# humidor_controller_v32.net
KiCad netlist of a schematic drawn in EAGLE
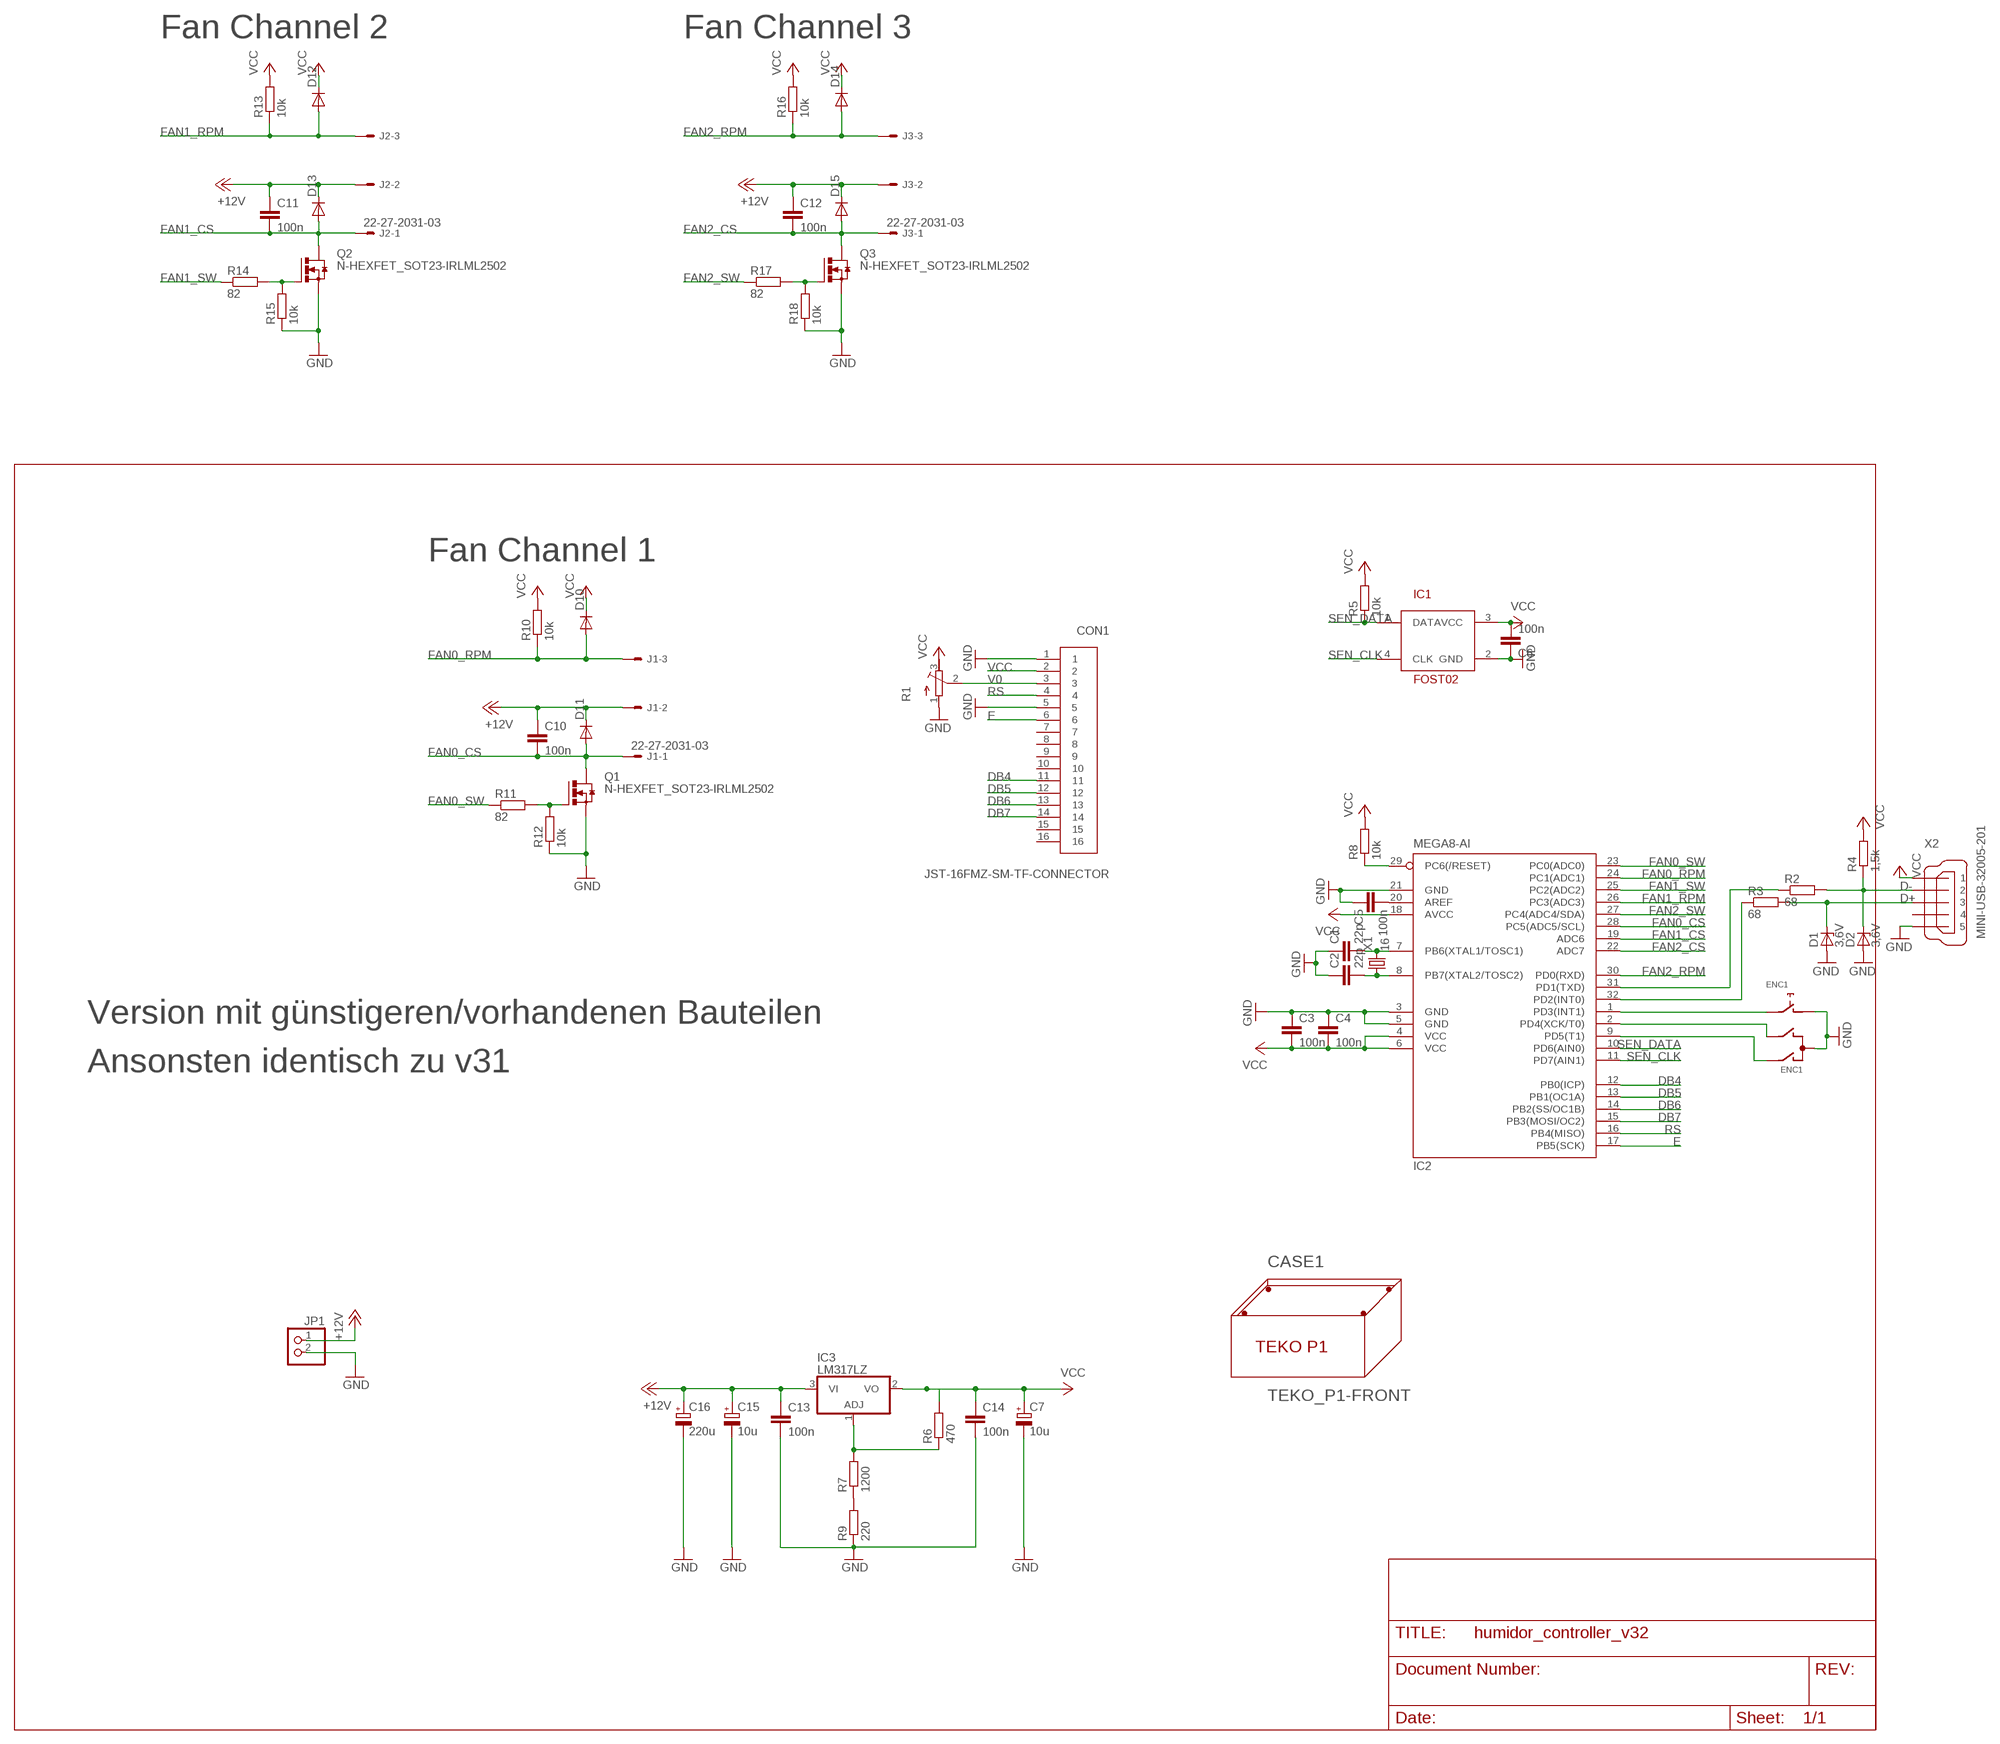
[diagram p0: schematic, sheet 1]

(export (version "E")
  (design (tool "Eeschema 10.0.6"))
  (components
    (comp (ref "C1")
      (value "22p")
      (footprint "eagle-import:C0805")
      (libsource (lib "eagle-import") (part "C-EUC0805"))
    )
    (comp (ref "C2")
      (value "22p")
      (footprint "eagle-import:C0805")
      (libsource (lib "eagle-import") (part "C-EUC0805"))
    )
    (comp (ref "C3")
      (value "100n")
      (footprint "eagle-import:C0805")
      (libsource (lib "eagle-import") (part "resistor_C-EUC0805"))
    )
    (comp (ref "C4")
      (value "100n")
      (footprint "eagle-import:C0805")
      (libsource (lib "eagle-import") (part "resistor_C-EUC0805"))
    )
    (comp (ref "C5")
      (value "100n")
      (footprint "eagle-import:C0805")
      (libsource (lib "eagle-import") (part "resistor_C-EUC0805"))
    )
    (comp (ref "C6")
      (value "100n")
      (footprint "eagle-import:C0805")
      (libsource (lib "eagle-import") (part "resistor_C-EUC0805"))
    )
    (comp (ref "C7")
      (value "10u")
      (footprint "eagle-import:PANASONIC_D")
      (libsource (lib "eagle-import") (part "CPOL-EUD"))
    )
    (comp (ref "C10")
      (value "100n")
      (footprint "eagle-import:C0805")
      (libsource (lib "eagle-import") (part "resistor_C-EUC0805"))
    )
    (comp (ref "C11")
      (value "100n")
      (footprint "eagle-import:C0805")
      (libsource (lib "eagle-import") (part "resistor_C-EUC0805"))
    )
    (comp (ref "C12")
      (value "100n")
      (footprint "eagle-import:C0805")
      (libsource (lib "eagle-import") (part "resistor_C-EUC0805"))
    )
    (comp (ref "C13")
      (value "100n")
      (footprint "eagle-import:C0805")
      (libsource (lib "eagle-import") (part "C-EUC0805"))
    )
    (comp (ref "C14")
      (value "100n")
      (footprint "eagle-import:C0805")
      (libsource (lib "eagle-import") (part "C-EUC0805"))
    )
    (comp (ref "C15")
      (value "10u")
      (footprint "eagle-import:PANASONIC_D")
      (libsource (lib "eagle-import") (part "CPOL-EUD"))
    )
    (comp (ref "C16")
      (value "220u")
      (footprint "eagle-import:PANASONIC_G")
      (libsource (lib "eagle-import") (part "CPOL-EUG"))
    )
    (comp (ref "CASE1")
      (value "TEKO_P1-FRONT")
      (footprint "eagle-import:TEKO_P1_FRONT")
      (libsource (lib "eagle-import") (part "TEKO_P1-FRONT"))
    )
    (comp (ref "CON1")
      (value "JST-16FMZ-SM-TF-CONNECTOR")
      (footprint "eagle-import:FFC-16POS-SMT-1MM-HORIZ")
      (libsource (lib "eagle-import") (part "JST-16FMZ-SM-TF-CONNECTOR"))
    )
    (comp (ref "D1")
      (value "3,6V")
      (footprint "eagle-import:DO34Z7")
      (libsource (lib "eagle-import") (part "ZENER-DIODEDO34-7"))
    )
    (comp (ref "D2")
      (value "3,6V")
      (footprint "eagle-import:DO34Z7")
      (libsource (lib "eagle-import") (part "ZENER-DIODEDO34-7"))
    )
    (comp (ref "D10")
      (value "DIODE-SOD323-R")
      (footprint "eagle-import:SOD323-R")
      (libsource (lib "eagle-import") (part "DIODE-SOD323-R"))
    )
    (comp (ref "D11")
      (value "DIODE-SOD323-R")
      (footprint "eagle-import:SOD323-R")
      (libsource (lib "eagle-import") (part "DIODE-SOD323-R"))
    )
    (comp (ref "D12")
      (value "DIODE-SOD323-R")
      (footprint "eagle-import:SOD323-R")
      (libsource (lib "eagle-import") (part "DIODE-SOD323-R"))
    )
    (comp (ref "D13")
      (value "DIODE-SOD323-R")
      (footprint "eagle-import:SOD323-R")
      (libsource (lib "eagle-import") (part "DIODE-SOD323-R"))
    )
    (comp (ref "D14")
      (value "DIODE-SOD323-R")
      (footprint "eagle-import:SOD323-R")
      (libsource (lib "eagle-import") (part "DIODE-SOD323-R"))
    )
    (comp (ref "D15")
      (value "DIODE-SOD323-R")
      (footprint "eagle-import:SOD323-R")
      (libsource (lib "eagle-import") (part "DIODE-SOD323-R"))
    )
    (comp (ref "ENC1")
      (value "NOBLE_RE0124")
      (footprint "eagle-import:RE0124")
      (libsource (lib "eagle-import") (part "NOBLE_RE0124"))
    )
    (comp (ref "IC1")
      (value "FOST02")
      (footprint "eagle-import:FOST02")
      (libsource (lib "eagle-import") (part "FOST02"))
    )
    (comp (ref "IC2")
      (value "MEGA8-AI")
      (footprint "eagle-import:TQFP32-08")
      (libsource (lib "eagle-import") (part "MEGA8-AI"))
    )
    (comp (ref "IC3")
      (value "LM317LZ")
      (footprint "eagle-import:TO92")
      (libsource (lib "eagle-import") (part "317LZLM"))
    )
    (comp (ref "J1")
      (value "22-27-2031-03")
      (footprint "eagle-import:6410-03")
      (libsource (lib "eagle-import") (part "22-?-0327-2031"))
    )
    (comp (ref "J2")
      (value "22-27-2031-03")
      (footprint "eagle-import:6410-03")
      (libsource (lib "eagle-import") (part "22-?-0327-2031"))
    )
    (comp (ref "J3")
      (value "22-27-2031-03")
      (footprint "eagle-import:6410-03")
      (libsource (lib "eagle-import") (part "22-?-0327-2031"))
    )
    (comp (ref "JP1")
      (value "PINHD-1X2")
      (footprint "eagle-import:1X02")
      (libsource (lib "eagle-import") (part "PINHD-1X2"))
    )
    (comp (ref "Q1")
      (value "N-HEXFET_SOT23-IRLML2502")
      (footprint "eagle-import:SOT23")
      (libsource (lib "eagle-import") (part "N-HEXFET_?-SOT23IRLML2502"))
    )
    (comp (ref "Q2")
      (value "N-HEXFET_SOT23-IRLML2502")
      (footprint "eagle-import:SOT23")
      (libsource (lib "eagle-import") (part "N-HEXFET_?-SOT23IRLML2502"))
    )
    (comp (ref "Q3")
      (value "N-HEXFET_SOT23-IRLML2502")
      (footprint "eagle-import:SOT23")
      (libsource (lib "eagle-import") (part "N-HEXFET_?-SOT23IRLML2502"))
    )
    (comp (ref "R1")
      (value "R-TRIMM64W")
      (footprint "eagle-import:RTRIM64W")
      (libsource (lib "eagle-import") (part "R-TRIMM64W"))
    )
    (comp (ref "R2")
      (value "68")
      (footprint "eagle-import:R0805")
      (libsource (lib "eagle-import") (part "R-EU_R0805"))
    )
    (comp (ref "R3")
      (value "68")
      (footprint "eagle-import:R0805")
      (libsource (lib "eagle-import") (part "R-EU_R0805"))
    )
    (comp (ref "R4")
      (value "1,5k")
      (footprint "eagle-import:R0805")
      (libsource (lib "eagle-import") (part "R-EU_R0805"))
    )
    (comp (ref "R5")
      (value "10k")
      (footprint "eagle-import:R0805")
      (libsource (lib "eagle-import") (part "R-EU_R0805"))
    )
    (comp (ref "R6")
      (value "470")
      (footprint "eagle-import:R0805")
      (libsource (lib "eagle-import") (part "R-EU_R0805"))
    )
    (comp (ref "R7")
      (value "1200")
      (footprint "eagle-import:R0805")
      (libsource (lib "eagle-import") (part "R-EU_R0805"))
    )
    (comp (ref "R8")
      (value "10k")
      (footprint "eagle-import:R0805")
      (libsource (lib "eagle-import") (part "R-EU_R0805"))
    )
    (comp (ref "R9")
      (value "220")
      (footprint "eagle-import:R0805")
      (libsource (lib "eagle-import") (part "R-EU_R0805"))
    )
    (comp (ref "R10")
      (value "10k")
      (footprint "eagle-import:R0805")
      (libsource (lib "eagle-import") (part "R-EU_R0805"))
    )
    (comp (ref "R11")
      (value "82")
      (footprint "eagle-import:R0805")
      (libsource (lib "eagle-import") (part "R-EU_R0805"))
    )
    (comp (ref "R12")
      (value "10k")
      (footprint "eagle-import:R0805")
      (libsource (lib "eagle-import") (part "R-EU_R0805"))
    )
    (comp (ref "R13")
      (value "10k")
      (footprint "eagle-import:R0805")
      (libsource (lib "eagle-import") (part "R-EU_R0805"))
    )
    (comp (ref "R14")
      (value "82")
      (footprint "eagle-import:R0805")
      (libsource (lib "eagle-import") (part "R-EU_R0805"))
    )
    (comp (ref "R15")
      (value "10k")
      (footprint "eagle-import:R0805")
      (libsource (lib "eagle-import") (part "R-EU_R0805"))
    )
    (comp (ref "R16")
      (value "10k")
      (footprint "eagle-import:R0805")
      (libsource (lib "eagle-import") (part "R-EU_R0805"))
    )
    (comp (ref "R17")
      (value "82")
      (footprint "eagle-import:R0805")
      (libsource (lib "eagle-import") (part "R-EU_R0805"))
    )
    (comp (ref "R18")
      (value "10k")
      (footprint "eagle-import:R0805")
      (libsource (lib "eagle-import") (part "R-EU_R0805"))
    )
    (comp (ref "X1")
      (value "16")
      (footprint "eagle-import:HC49UP")
      (libsource (lib "eagle-import") (part "CRYSTALHC49UP"))
    )
    (comp (ref "X2")
      (value "MINI-USB-32005-201")
      (footprint "eagle-import:32005-201")
      (libsource (lib "eagle-import") (part "MINI-USB-32005-201"))
    )
  )
  (nets
    (net (code "1") (name "+12V") (class "Default")
      (node (ref "C10") (pin "1") (pinfunction "1_1") (pintype "passive"))
      (node (ref "C11") (pin "1") (pinfunction "1_1") (pintype "passive"))
      (node (ref "C12") (pin "1") (pinfunction "1_1") (pintype "passive"))
      (node (ref "C13") (pin "1") (pinfunction "1_1") (pintype "passive"))
      (node (ref "C15") (pin "+") (pinfunction "+_+") (pintype "passive"))
      (node (ref "C16") (pin "+") (pinfunction "+_+") (pintype "passive"))
      (node (ref "D11") (pin "C") (pinfunction "C_C") (pintype "passive"))
      (node (ref "D13") (pin "C") (pinfunction "C_C") (pintype "passive"))
      (node (ref "D15") (pin "C") (pinfunction "C_C") (pintype "passive"))
      (node (ref "IC3") (pin "3") (pinfunction "VI_3") (pintype "input"))
      (node (ref "J1") (pin "2") (pinfunction "S_2") (pintype "passive"))
      (node (ref "J2") (pin "2") (pinfunction "S_2") (pintype "passive"))
      (node (ref "J3") (pin "2") (pinfunction "S_2") (pintype "passive"))
      (node (ref "JP1") (pin "1") (pinfunction "1_1") (pintype "passive"))
    )
    (net (code "2") (name "/D+") (class "Default")
      (node (ref "D1") (pin "C") (pinfunction "C_C") (pintype "passive"))
      (node (ref "R3") (pin "2") (pinfunction "2_2") (pintype "passive"))
      (node (ref "X2") (pin "3") (pinfunction "3_3") (pintype "passive"))
    )
    (net (code "3") (name "/D-") (class "Default")
      (node (ref "D2") (pin "C") (pinfunction "C_C") (pintype "passive"))
      (node (ref "R2") (pin "2") (pinfunction "2_2") (pintype "passive"))
      (node (ref "R4") (pin "1") (pinfunction "1_1") (pintype "passive"))
      (node (ref "X2") (pin "2") (pinfunction "2_2") (pintype "passive"))
    )
    (net (code "4") (name "/DB4") (class "Default")
      (node (ref "CON1") (pin "11") (pinfunction "11_11") (pintype "bidirectional"))
      (node (ref "IC2") (pin "12") (pinfunction "PB0(ICP)_12") (pintype "bidirectional"))
    )
    (net (code "5") (name "/DB5") (class "Default")
      (node (ref "CON1") (pin "12") (pinfunction "12_12") (pintype "bidirectional"))
      (node (ref "IC2") (pin "13") (pinfunction "PB1(OC1A)_13") (pintype "bidirectional"))
    )
    (net (code "6") (name "/DB6") (class "Default")
      (node (ref "CON1") (pin "13") (pinfunction "13_13") (pintype "bidirectional"))
      (node (ref "IC2") (pin "14") (pinfunction "PB2(SS/OC1B)_14") (pintype "bidirectional"))
    )
    (net (code "7") (name "/DB7") (class "Default")
      (node (ref "CON1") (pin "14") (pinfunction "14_14") (pintype "bidirectional"))
      (node (ref "IC2") (pin "15") (pinfunction "PB3(MOSI/OC2)_15") (pintype "bidirectional"))
    )
    (net (code "8") (name "/E") (class "Default")
      (node (ref "CON1") (pin "6") (pinfunction "6_6") (pintype "bidirectional"))
      (node (ref "IC2") (pin "17") (pinfunction "PB5(SCK)_17") (pintype "bidirectional"))
    )
    (net (code "9") (name "/FAN0_CS") (class "Default")
      (node (ref "C10") (pin "2") (pinfunction "2_2") (pintype "passive"))
      (node (ref "D11") (pin "A") (pinfunction "A_A") (pintype "passive"))
      (node (ref "IC2") (pin "28") (pinfunction "PC5(ADC5/SCL)_28") (pintype "bidirectional"))
      (node (ref "J1") (pin "1") (pinfunction "S_1") (pintype "passive"))
      (node (ref "Q1") (pin "3") (pinfunction "D_3") (pintype "passive"))
    )
    (net (code "10") (name "/FAN0_RPM") (class "Default")
      (node (ref "D10") (pin "A") (pinfunction "A_A") (pintype "passive"))
      (node (ref "IC2") (pin "24") (pinfunction "PC1(ADC1)_24") (pintype "bidirectional"))
      (node (ref "J1") (pin "3") (pinfunction "S_3") (pintype "passive"))
      (node (ref "R10") (pin "1") (pinfunction "1_1") (pintype "passive"))
    )
    (net (code "11") (name "/FAN0_SW") (class "Default")
      (node (ref "IC2") (pin "23") (pinfunction "PC0(ADC0)_23") (pintype "bidirectional"))
      (node (ref "R11") (pin "1") (pinfunction "1_1") (pintype "passive"))
    )
    (net (code "12") (name "/FAN1_CS") (class "Default")
      (node (ref "C11") (pin "2") (pinfunction "2_2") (pintype "passive"))
      (node (ref "D13") (pin "A") (pinfunction "A_A") (pintype "passive"))
      (node (ref "IC2") (pin "19") (pinfunction "ADC6_19") (pintype "bidirectional"))
      (node (ref "J2") (pin "1") (pinfunction "S_1") (pintype "passive"))
      (node (ref "Q2") (pin "3") (pinfunction "D_3") (pintype "passive"))
    )
    (net (code "13") (name "/FAN1_RPM") (class "Default")
      (node (ref "D12") (pin "A") (pinfunction "A_A") (pintype "passive"))
      (node (ref "IC2") (pin "26") (pinfunction "PC3(ADC3)_26") (pintype "bidirectional"))
      (node (ref "J2") (pin "3") (pinfunction "S_3") (pintype "passive"))
      (node (ref "R13") (pin "1") (pinfunction "1_1") (pintype "passive"))
    )
    (net (code "14") (name "/FAN1_SW") (class "Default")
      (node (ref "IC2") (pin "25") (pinfunction "PC2(ADC2)_25") (pintype "bidirectional"))
      (node (ref "R14") (pin "1") (pinfunction "1_1") (pintype "passive"))
    )
    (net (code "15") (name "/FAN2_CS") (class "Default")
      (node (ref "C12") (pin "2") (pinfunction "2_2") (pintype "passive"))
      (node (ref "D15") (pin "A") (pinfunction "A_A") (pintype "passive"))
      (node (ref "IC2") (pin "22") (pinfunction "ADC7_22") (pintype "bidirectional"))
      (node (ref "J3") (pin "1") (pinfunction "S_1") (pintype "passive"))
      (node (ref "Q3") (pin "3") (pinfunction "D_3") (pintype "passive"))
    )
    (net (code "16") (name "/FAN2_RPM") (class "Default")
      (node (ref "D14") (pin "A") (pinfunction "A_A") (pintype "passive"))
      (node (ref "IC2") (pin "30") (pinfunction "PD0(RXD)_30") (pintype "bidirectional"))
      (node (ref "J3") (pin "3") (pinfunction "S_3") (pintype "passive"))
      (node (ref "R16") (pin "1") (pinfunction "1_1") (pintype "passive"))
    )
    (net (code "17") (name "/FAN2_SW") (class "Default")
      (node (ref "IC2") (pin "27") (pinfunction "PC4(ADC4/SDA)_27") (pintype "bidirectional"))
      (node (ref "R17") (pin "1") (pinfunction "1_1") (pintype "passive"))
    )
    (net (code "18") (name "/RS") (class "Default")
      (node (ref "CON1") (pin "4") (pinfunction "4_4") (pintype "bidirectional"))
      (node (ref "IC2") (pin "16") (pinfunction "PB4(MISO)_16") (pintype "bidirectional"))
    )
    (net (code "19") (name "/SEN_CLK") (class "Default")
      (node (ref "IC1") (pin "4") (pinfunction "CLK_4") (pintype "input"))
      (node (ref "IC2") (pin "11") (pinfunction "PD7(AIN1)_11") (pintype "bidirectional"))
    )
    (net (code "20") (name "/SEN_DATA") (class "Default")
      (node (ref "IC1") (pin "1") (pinfunction "DATA_1") (pintype "bidirectional"))
      (node (ref "IC2") (pin "10") (pinfunction "PD6(AIN0)_10") (pintype "bidirectional"))
      (node (ref "R5") (pin "1") (pinfunction "1_1") (pintype "passive"))
    )
    (net (code "21") (name "/V0") (class "Default")
      (node (ref "CON1") (pin "3") (pinfunction "3_3") (pintype "bidirectional"))
      (node (ref "R1") (pin "2") (pinfunction "S_2") (pintype "passive"))
    )
    (net (code "22") (name "GND") (class "Default")
      (node (ref "C1") (pin "1") (pinfunction "1_1") (pintype "passive"))
      (node (ref "C13") (pin "2") (pinfunction "2_2") (pintype "passive"))
      (node (ref "C14") (pin "2") (pinfunction "2_2") (pintype "passive"))
      (node (ref "C15") (pin "-") (pinfunction "-_-") (pintype "passive"))
      (node (ref "C16") (pin "-") (pinfunction "-_-") (pintype "passive"))
      (node (ref "C2") (pin "1") (pinfunction "1_1") (pintype "passive"))
      (node (ref "C3") (pin "1") (pinfunction "1_1") (pintype "passive"))
      (node (ref "C4") (pin "1") (pinfunction "1_1") (pintype "passive"))
      (node (ref "C5") (pin "1") (pinfunction "1_1") (pintype "passive"))
      (node (ref "C6") (pin "1") (pinfunction "1_1") (pintype "passive"))
      (node (ref "C7") (pin "-") (pinfunction "-_-") (pintype "passive"))
      (node (ref "CON1") (pin "1") (pinfunction "1_1") (pintype "bidirectional"))
      (node (ref "CON1") (pin "5") (pinfunction "5_5") (pintype "bidirectional"))
      (node (ref "D1") (pin "A") (pinfunction "A_A") (pintype "passive"))
      (node (ref "D2") (pin "A") (pinfunction "A_A") (pintype "passive"))
      (node (ref "ENC1") (pin "+") (pinfunction "1_+") (pintype "passive"))
      (node (ref "ENC1") (pin "C") (pinfunction "C_C") (pintype "passive"))
      (node (ref "IC1") (pin "2") (pinfunction "GND_2") (pintype "power_in"))
      (node (ref "IC2") (pin "21") (pinfunction "GND_21") (pintype "power_in"))
      (node (ref "IC2") (pin "3") (pinfunction "GND_3") (pintype "power_in"))
      (node (ref "IC2") (pin "5") (pinfunction "GND_5") (pintype "power_in"))
      (node (ref "JP1") (pin "2") (pinfunction "2_2") (pintype "passive"))
      (node (ref "Q1") (pin "2") (pinfunction "S_2") (pintype "passive"))
      (node (ref "Q2") (pin "2") (pinfunction "S_2") (pintype "passive"))
      (node (ref "Q3") (pin "2") (pinfunction "S_2") (pintype "passive"))
      (node (ref "R1") (pin "1") (pinfunction "E_1") (pintype "passive"))
      (node (ref "R12") (pin "1") (pinfunction "1_1") (pintype "passive"))
      (node (ref "R15") (pin "1") (pinfunction "1_1") (pintype "passive"))
      (node (ref "R18") (pin "1") (pinfunction "1_1") (pintype "passive"))
      (node (ref "R9") (pin "1") (pinfunction "1_1") (pintype "passive"))
      (node (ref "X2") (pin "5") (pinfunction "5_5") (pintype "passive"))
    )
    (net (code "23") (name "Net-(ENC1B-2)") (class "Default")
      (node (ref "ENC1") (pin "-") (pinfunction "2_-") (pintype "passive"))
      (node (ref "IC2") (pin "1") (pinfunction "PD3(INT1)_1") (pintype "bidirectional"))
    )
    (net (code "24") (name "Net-(IC2-AREF)") (class "Default")
      (node (ref "C5") (pin "2") (pinfunction "2_2") (pintype "passive"))
      (node (ref "IC2") (pin "20") (pinfunction "AREF_20") (pintype "passive"))
    )
    (net (code "25") (name "Net-(IC2-PB6(XTAL1{slash}TOSC1))") (class "Default")
      (node (ref "C1") (pin "2") (pinfunction "2_2") (pintype "passive"))
      (node (ref "IC2") (pin "7") (pinfunction "PB6(XTAL1/TOSC1)_7") (pintype "bidirectional"))
      (node (ref "X1") (pin "2") (pinfunction "2_2") (pintype "passive"))
    )
    (net (code "26") (name "Net-(IC2-PB7(XTAL2{slash}TOSC2))") (class "Default")
      (node (ref "C2") (pin "2") (pinfunction "2_2") (pintype "passive"))
      (node (ref "IC2") (pin "8") (pinfunction "PB7(XTAL2/TOSC2)_8") (pintype "bidirectional"))
      (node (ref "X1") (pin "1") (pinfunction "1_1") (pintype "passive"))
    )
    (net (code "27") (name "Net-(IC2-PC6({slash}RESET))") (class "Default")
      (node (ref "IC2") (pin "29") (pinfunction "PC6(/RESET)_29") (pintype "bidirectional"))
      (node (ref "R8") (pin "1") (pinfunction "1_1") (pintype "passive"))
    )
    (net (code "28") (name "Net-(IC2-PD1(TXD))") (class "Default")
      (node (ref "IC2") (pin "31") (pinfunction "PD1(TXD)_31") (pintype "bidirectional"))
      (node (ref "R2") (pin "1") (pinfunction "1_1") (pintype "passive"))
    )
    (net (code "29") (name "Net-(IC2-PD2(INT0))") (class "Default")
      (node (ref "IC2") (pin "32") (pinfunction "PD2(INT0)_32") (pintype "bidirectional"))
      (node (ref "R3") (pin "1") (pinfunction "1_1") (pintype "passive"))
    )
    (net (code "30") (name "Net-(IC2-PD4(XCK{slash}T0))") (class "Default")
      (node (ref "ENC1") (pin "B") (pinfunction "B_B") (pintype "passive"))
      (node (ref "IC2") (pin "2") (pinfunction "PD4(XCK/T0)_2") (pintype "bidirectional"))
    )
    (net (code "31") (name "Net-(IC2-PD5(T1))") (class "Default")
      (node (ref "ENC1") (pin "A") (pinfunction "A_A") (pintype "passive"))
      (node (ref "IC2") (pin "9") (pinfunction "PD5(T1)_9") (pintype "bidirectional"))
    )
    (net (code "32") (name "Net-(IC3-ADJ)") (class "Default")
      (node (ref "IC3") (pin "1") (pinfunction "ADJ_1") (pintype "input"))
      (node (ref "R6") (pin "1") (pinfunction "1_1") (pintype "passive"))
      (node (ref "R7") (pin "2") (pinfunction "2_2") (pintype "passive"))
    )
    (net (code "33") (name "Net-(Q1-G)") (class "Default")
      (node (ref "Q1") (pin "1") (pinfunction "G_1") (pintype "passive"))
      (node (ref "R11") (pin "2") (pinfunction "2_2") (pintype "passive"))
      (node (ref "R12") (pin "2") (pinfunction "2_2") (pintype "passive"))
    )
    (net (code "34") (name "Net-(Q2-G)") (class "Default")
      (node (ref "Q2") (pin "1") (pinfunction "G_1") (pintype "passive"))
      (node (ref "R14") (pin "2") (pinfunction "2_2") (pintype "passive"))
      (node (ref "R15") (pin "2") (pinfunction "2_2") (pintype "passive"))
    )
    (net (code "35") (name "Net-(Q3-G)") (class "Default")
      (node (ref "Q3") (pin "1") (pinfunction "G_1") (pintype "passive"))
      (node (ref "R17") (pin "2") (pinfunction "2_2") (pintype "passive"))
      (node (ref "R18") (pin "2") (pinfunction "2_2") (pintype "passive"))
    )
    (net (code "36") (name "Net-(R7-Pad1)") (class "Default")
      (node (ref "R7") (pin "1") (pinfunction "1_1") (pintype "passive"))
      (node (ref "R9") (pin "2") (pinfunction "2_2") (pintype "passive"))
    )
    (net (code "37") (name "VCC") (class "Default")
      (node (ref "C14") (pin "1") (pinfunction "1_1") (pintype "passive"))
      (node (ref "C3") (pin "2") (pinfunction "2_2") (pintype "passive"))
      (node (ref "C4") (pin "2") (pinfunction "2_2") (pintype "passive"))
      (node (ref "C6") (pin "2") (pinfunction "2_2") (pintype "passive"))
      (node (ref "C7") (pin "+") (pinfunction "+_+") (pintype "passive"))
      (node (ref "CON1") (pin "2") (pinfunction "2_2") (pintype "bidirectional"))
      (node (ref "D10") (pin "C") (pinfunction "C_C") (pintype "passive"))
      (node (ref "D12") (pin "C") (pinfunction "C_C") (pintype "passive"))
      (node (ref "D14") (pin "C") (pinfunction "C_C") (pintype "passive"))
      (node (ref "IC1") (pin "3") (pinfunction "VCC_3") (pintype "power_in"))
      (node (ref "IC2") (pin "18") (pinfunction "AVCC_18") (pintype "power_in"))
      (node (ref "IC2") (pin "4") (pinfunction "VCC_4") (pintype "power_in"))
      (node (ref "IC2") (pin "6") (pinfunction "VCC_6") (pintype "power_in"))
      (node (ref "IC3") (pin "2") (pinfunction "VO_2") (pintype "passive"))
      (node (ref "R1") (pin "3") (pinfunction "A_3") (pintype "passive"))
      (node (ref "R10") (pin "2") (pinfunction "2_2") (pintype "passive"))
      (node (ref "R13") (pin "2") (pinfunction "2_2") (pintype "passive"))
      (node (ref "R16") (pin "2") (pinfunction "2_2") (pintype "passive"))
      (node (ref "R4") (pin "2") (pinfunction "2_2") (pintype "passive"))
      (node (ref "R5") (pin "2") (pinfunction "2_2") (pintype "passive"))
      (node (ref "R6") (pin "2") (pinfunction "2_2") (pintype "passive"))
      (node (ref "R8") (pin "2") (pinfunction "2_2") (pintype "passive"))
      (node (ref "X2") (pin "1") (pinfunction "1_1") (pintype "passive"))
    )
    (net (code "38") (name "unconnected-(CON1-Pad7)") (class "Default")
      (node (ref "CON1") (pin "7") (pinfunction "7_7") (pintype "bidirectional"))
    )
    (net (code "39") (name "unconnected-(CON1-Pad8)") (class "Default")
      (node (ref "CON1") (pin "8") (pinfunction "8_8") (pintype "bidirectional"))
    )
    (net (code "40") (name "unconnected-(CON1-Pad9)") (class "Default")
      (node (ref "CON1") (pin "9") (pinfunction "9_9") (pintype "bidirectional"))
    )
    (net (code "41") (name "unconnected-(CON1-Pad10)") (class "Default")
      (node (ref "CON1") (pin "10") (pinfunction "10_10") (pintype "bidirectional"))
    )
    (net (code "42") (name "unconnected-(CON1-Pad15)") (class "Default")
      (node (ref "CON1") (pin "15") (pinfunction "15_15") (pintype "bidirectional"))
    )
    (net (code "43") (name "unconnected-(CON1-Pad16)") (class "Default")
      (node (ref "CON1") (pin "16") (pinfunction "16_16") (pintype "bidirectional"))
    )
    (net (code "44") (name "unconnected-(X2-Pad4)") (class "Default")
      (node (ref "X2") (pin "4") (pinfunction "4_4") (pintype "passive"))
    )
  )
)
